# darwin-lora.net
KiCad netlist of a schematic drawn in EAGLE
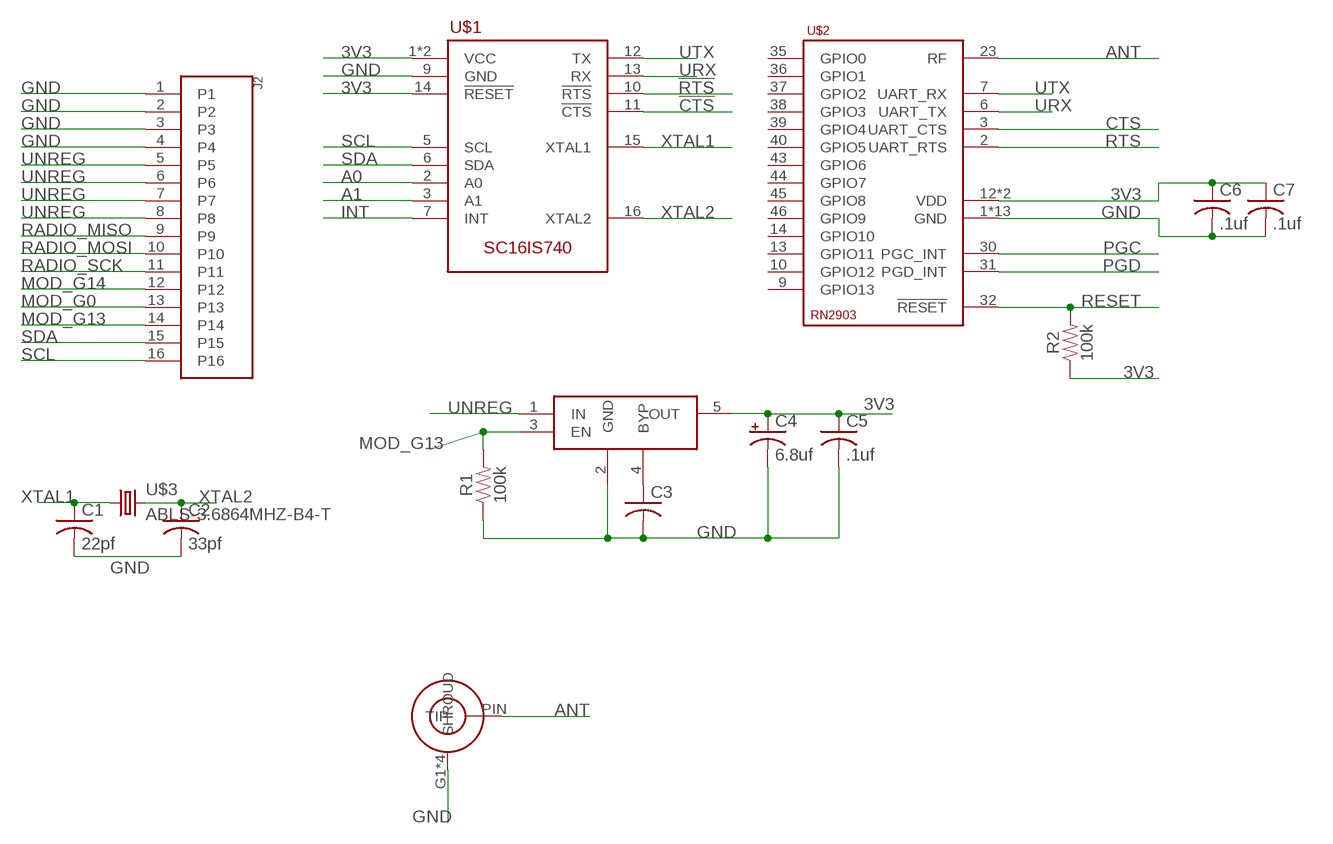
[diagram p0: schematic, sheet 1]

(export (version "E")
  (design (tool "Eeschema 10.0.6"))
  (components
    (comp (ref "C1")
      (value "22pf")
      (footprint "eagle-import:C0603K")
      (libsource (lib "eagle-import") (part "C-USC0603K"))
    )
    (comp (ref "C2")
      (value "33pf")
      (footprint "eagle-import:C0603K")
      (libsource (lib "eagle-import") (part "C-USC0603K"))
    )
    (comp (ref "C3")
      (value "C-USC0603K")
      (footprint "eagle-import:C0603K")
      (libsource (lib "eagle-import") (part "C-USC0603K"))
    )
    (comp (ref "C4")
      (value "6.8uf")
      (footprint "eagle-import:A_3216-18R")
      (libsource (lib "eagle-import") (part "CPOL-USA/3216-18R"))
    )
    (comp (ref "C5")
      (value ".1uf")
      (footprint "eagle-import:C0603K")
      (libsource (lib "eagle-import") (part "C-USC0603K"))
    )
    (comp (ref "C6")
      (value ".1uf")
      (footprint "eagle-import:C0603K")
      (libsource (lib "eagle-import") (part "C-USC0603K"))
    )
    (comp (ref "C7")
      (value ".1uf")
      (footprint "eagle-import:C0603K")
      (libsource (lib "eagle-import") (part "C-USC0603K"))
    )
    (comp (ref "J2")
      (value "505110-1692")
      (footprint "eagle-import:505110-1692")
      (libsource (lib "eagle-import") (part "505110-1692"))
    )
    (comp (ref "R1")
      (value "100k")
      (footprint "eagle-import:0603")
      (libsource (lib "eagle-import") (part "100KOHM-0603-1/10W-1%"))
    )
    (comp (ref "R2")
      (value "100k")
      (footprint "eagle-import:0603")
      (libsource (lib "eagle-import") (part "100KOHM-0603-1/10W-1%"))
    )
    (comp (ref "U$1")
      (value "SC16IS740")
      (footprint "eagle-import:SOP65P640X110-16")
      (libsource (lib "eagle-import") (part "SC16IS740"))
    )
    (comp (ref "U$2")
      (value "RN2903")
      (footprint "eagle-import:RN2903")
      (libsource (lib "eagle-import") (part "RN2903"))
    )
    (comp (ref "U$3")
      (value "ABLS-3.6864MHZ-B4-T")
      (footprint "eagle-import:ABLS")
      (libsource (lib "eagle-import") (part "ABLS-3.6864MHZ-B4-T"))
    )
    (comp (ref "U$4")
      (value "MIC5219-3.3YM5-TR")
      (footprint "eagle-import:SOT95P280X145-5")
      (libsource (lib "eagle-import") (part "MIC5219-3.3YM5-TR"))
    )
    (comp (ref "U$5")
      (value "5-1814832-1")
      (footprint "eagle-import:5-1814832-1")
      (libsource (lib "eagle-import") (part "5-1814832-1"))
    )
  )
  (nets
    (net (code "1") (name "/3V3") (class "Default")
      (node (ref "C4") (pin "+") (pinfunction "+_+") (pintype "passive"))
      (node (ref "C5") (pin "1") (pinfunction "1_1") (pintype "passive"))
      (node (ref "C6") (pin "1") (pinfunction "1_1") (pintype "passive"))
      (node (ref "C7") (pin "1") (pinfunction "1_1") (pintype "passive"))
      (node (ref "R2") (pin "1") (pinfunction "1_1") (pintype "passive"))
      (node (ref "U$1") (pin "1") (pinfunction "VCC_1") (pintype "bidirectional"))
      (node (ref "U$1") (pin "14") (pinfunction "~{RESET}_14") (pintype "bidirectional"))
      (node (ref "U$1") (pin "8") (pinfunction "VCC_8") (pintype "bidirectional"))
      (node (ref "U$2") (pin "12") (pinfunction "VDD_12") (pintype "bidirectional"))
      (node (ref "U$2") (pin "34") (pinfunction "VDD_34") (pintype "bidirectional"))
      (node (ref "U$4") (pin "5") (pinfunction "OUT_5") (pintype "bidirectional"))
    )
    (net (code "2") (name "/A0") (class "Default")
      (node (ref "U$1") (pin "2") (pinfunction "A0_2") (pintype "bidirectional"))
    )
    (net (code "3") (name "/A1") (class "Default")
      (node (ref "U$1") (pin "3") (pinfunction "A1_3") (pintype "bidirectional"))
    )
    (net (code "4") (name "/ANT") (class "Default")
      (node (ref "U$2") (pin "23") (pinfunction "RF_23") (pintype "bidirectional"))
      (node (ref "U$5") (pin "PIN") (pinfunction "TIP_PIN") (pintype "bidirectional"))
    )
    (net (code "5") (name "/CTS") (class "Default")
      (node (ref "U$2") (pin "3") (pinfunction "UART_CTS_3") (pintype "bidirectional"))
    )
    (net (code "6") (name "/GND") (class "Default")
      (node (ref "C1") (pin "2") (pinfunction "2_2") (pintype "passive"))
      (node (ref "C2") (pin "2") (pinfunction "2_2") (pintype "passive"))
      (node (ref "C3") (pin "2") (pinfunction "2_2") (pintype "passive"))
      (node (ref "C4") (pin "-") (pinfunction "-_-") (pintype "passive"))
      (node (ref "C5") (pin "2") (pinfunction "2_2") (pintype "passive"))
      (node (ref "C6") (pin "2") (pinfunction "2_2") (pintype "passive"))
      (node (ref "C7") (pin "2") (pinfunction "2_2") (pintype "passive"))
      (node (ref "J2") (pin "1") (pinfunction "P1_1") (pintype "bidirectional"))
      (node (ref "J2") (pin "2") (pinfunction "P2_2") (pintype "bidirectional"))
      (node (ref "J2") (pin "3") (pinfunction "P3_3") (pintype "bidirectional"))
      (node (ref "J2") (pin "4") (pinfunction "P4_4") (pintype "bidirectional"))
      (node (ref "R1") (pin "1") (pinfunction "1_1") (pintype "passive"))
      (node (ref "U$1") (pin "9") (pinfunction "GND_9") (pintype "bidirectional"))
      (node (ref "U$2") (pin "1") (pinfunction "GND_1") (pintype "bidirectional"))
      (node (ref "U$2") (pin "11") (pinfunction "GND_11") (pintype "bidirectional"))
      (node (ref "U$2") (pin "20") (pinfunction "GND_20") (pintype "bidirectional"))
      (node (ref "U$2") (pin "21") (pinfunction "GND_21") (pintype "bidirectional"))
      (node (ref "U$2") (pin "22") (pinfunction "GND_22") (pintype "bidirectional"))
      (node (ref "U$2") (pin "24") (pinfunction "GND_24") (pintype "bidirectional"))
      (node (ref "U$2") (pin "26") (pinfunction "GND_26") (pintype "bidirectional"))
      (node (ref "U$2") (pin "27") (pinfunction "GND_27") (pintype "bidirectional"))
      (node (ref "U$2") (pin "28") (pinfunction "GND_28") (pintype "bidirectional"))
      (node (ref "U$2") (pin "33") (pinfunction "GND_33") (pintype "bidirectional"))
      (node (ref "U$2") (pin "41") (pinfunction "GND_41") (pintype "bidirectional"))
      (node (ref "U$2") (pin "47") (pinfunction "GND_47") (pintype "bidirectional"))
      (node (ref "U$2") (pin "8") (pinfunction "GND_8") (pintype "bidirectional"))
      (node (ref "U$4") (pin "2") (pinfunction "GND_2") (pintype "bidirectional"))
      (node (ref "U$5") (pin "G1") (pinfunction "SHROUD_G1") (pintype "bidirectional"))
      (node (ref "U$5") (pin "G2") (pinfunction "SHROUD_G2") (pintype "bidirectional"))
      (node (ref "U$5") (pin "G3") (pinfunction "SHROUD_G3") (pintype "bidirectional"))
      (node (ref "U$5") (pin "G4") (pinfunction "SHROUD_G4") (pintype "bidirectional"))
    )
    (net (code "7") (name "/INT") (class "Default")
      (node (ref "U$1") (pin "7") (pinfunction "INT_7") (pintype "bidirectional"))
    )
    (net (code "8") (name "/MOD_G0") (class "Default")
      (node (ref "J2") (pin "13") (pinfunction "P13_13") (pintype "bidirectional"))
    )
    (net (code "9") (name "/MOD_G13") (class "Default")
      (node (ref "J2") (pin "14") (pinfunction "P14_14") (pintype "bidirectional"))
      (node (ref "R1") (pin "2") (pinfunction "2_2") (pintype "passive"))
      (node (ref "U$4") (pin "3") (pinfunction "EN_3") (pintype "bidirectional"))
    )
    (net (code "10") (name "/MOD_G14") (class "Default")
      (node (ref "J2") (pin "12") (pinfunction "P12_12") (pintype "bidirectional"))
    )
    (net (code "11") (name "/PGC") (class "Default")
      (node (ref "U$2") (pin "30") (pinfunction "PGC_INT_30") (pintype "bidirectional"))
    )
    (net (code "12") (name "/PGD") (class "Default")
      (node (ref "U$2") (pin "31") (pinfunction "PGD_INT_31") (pintype "bidirectional"))
    )
    (net (code "13") (name "/RADIO_MISO") (class "Default")
      (node (ref "J2") (pin "9") (pinfunction "P9_9") (pintype "bidirectional"))
    )
    (net (code "14") (name "/RADIO_MOSI") (class "Default")
      (node (ref "J2") (pin "10") (pinfunction "P10_10") (pintype "bidirectional"))
    )
    (net (code "15") (name "/RADIO_SCK") (class "Default")
      (node (ref "J2") (pin "11") (pinfunction "P11_11") (pintype "bidirectional"))
    )
    (net (code "16") (name "/RESET") (class "Default")
      (node (ref "R2") (pin "2") (pinfunction "2_2") (pintype "passive"))
      (node (ref "U$2") (pin "32") (pinfunction "~{RESET}_32") (pintype "bidirectional"))
    )
    (net (code "17") (name "/RTS") (class "Default")
      (node (ref "U$2") (pin "2") (pinfunction "UART_RTS_2") (pintype "bidirectional"))
    )
    (net (code "18") (name "/SCL") (class "Default")
      (node (ref "J2") (pin "16") (pinfunction "P16_16") (pintype "bidirectional"))
      (node (ref "U$1") (pin "5") (pinfunction "SCL_5") (pintype "bidirectional"))
    )
    (net (code "19") (name "/SDA") (class "Default")
      (node (ref "J2") (pin "15") (pinfunction "P15_15") (pintype "bidirectional"))
      (node (ref "U$1") (pin "6") (pinfunction "SDA_6") (pintype "bidirectional"))
    )
    (net (code "20") (name "/UNREG") (class "Default")
      (node (ref "J2") (pin "5") (pinfunction "P5_5") (pintype "bidirectional"))
      (node (ref "J2") (pin "6") (pinfunction "P6_6") (pintype "bidirectional"))
      (node (ref "J2") (pin "7") (pinfunction "P7_7") (pintype "bidirectional"))
      (node (ref "J2") (pin "8") (pinfunction "P8_8") (pintype "bidirectional"))
      (node (ref "U$4") (pin "1") (pinfunction "IN_1") (pintype "bidirectional"))
    )
    (net (code "21") (name "/URX") (class "Default")
      (node (ref "U$1") (pin "13") (pinfunction "RX_13") (pintype "bidirectional"))
      (node (ref "U$2") (pin "6") (pinfunction "UART_TX_6") (pintype "bidirectional"))
    )
    (net (code "22") (name "/UTX") (class "Default")
      (node (ref "U$1") (pin "12") (pinfunction "TX_12") (pintype "bidirectional"))
      (node (ref "U$2") (pin "7") (pinfunction "UART_RX_7") (pintype "bidirectional"))
    )
    (net (code "23") (name "/XTAL1") (class "Default")
      (node (ref "C1") (pin "1") (pinfunction "1_1") (pintype "passive"))
      (node (ref "U$1") (pin "15") (pinfunction "XTAL1_15") (pintype "bidirectional"))
      (node (ref "U$3") (pin "P$1") (pinfunction "1_P$1") (pintype "passive"))
    )
    (net (code "24") (name "/XTAL2") (class "Default")
      (node (ref "C2") (pin "1") (pinfunction "1_1") (pintype "passive"))
      (node (ref "U$1") (pin "16") (pinfunction "XTAL2_16") (pintype "bidirectional"))
      (node (ref "U$3") (pin "P$2") (pinfunction "2_P$2") (pintype "passive"))
    )
    (net (code "25") (name "/~{CTS}") (class "Default")
      (node (ref "U$1") (pin "11") (pinfunction "~{CTS}_11") (pintype "bidirectional"))
    )
    (net (code "26") (name "/~{RTS}") (class "Default")
      (node (ref "U$1") (pin "10") (pinfunction "~{RTS}_10") (pintype "bidirectional"))
    )
    (net (code "27") (name "Net-(U$4-BYP)") (class "Default")
      (node (ref "C3") (pin "1") (pinfunction "1_1") (pintype "passive"))
      (node (ref "U$4") (pin "4") (pinfunction "BYP_4") (pintype "bidirectional"))
    )
    (net (code "28") (name "unconnected-(U$2-GPIO0-Pad35)") (class "Default")
      (node (ref "U$2") (pin "35") (pinfunction "GPIO0_35") (pintype "bidirectional"))
    )
    (net (code "29") (name "unconnected-(U$2-GPIO1-Pad36)") (class "Default")
      (node (ref "U$2") (pin "36") (pinfunction "GPIO1_36") (pintype "bidirectional"))
    )
    (net (code "30") (name "unconnected-(U$2-GPIO2-Pad37)") (class "Default")
      (node (ref "U$2") (pin "37") (pinfunction "GPIO2_37") (pintype "bidirectional"))
    )
    (net (code "31") (name "unconnected-(U$2-GPIO3-Pad38)") (class "Default")
      (node (ref "U$2") (pin "38") (pinfunction "GPIO3_38") (pintype "bidirectional"))
    )
    (net (code "32") (name "unconnected-(U$2-GPIO4-Pad39)") (class "Default")
      (node (ref "U$2") (pin "39") (pinfunction "GPIO4_39") (pintype "bidirectional"))
    )
    (net (code "33") (name "unconnected-(U$2-GPIO5-Pad40)") (class "Default")
      (node (ref "U$2") (pin "40") (pinfunction "GPIO5_40") (pintype "bidirectional"))
    )
    (net (code "34") (name "unconnected-(U$2-GPIO6-Pad43)") (class "Default")
      (node (ref "U$2") (pin "43") (pinfunction "GPIO6_43") (pintype "bidirectional"))
    )
    (net (code "35") (name "unconnected-(U$2-GPIO7-Pad44)") (class "Default")
      (node (ref "U$2") (pin "44") (pinfunction "GPIO7_44") (pintype "bidirectional"))
    )
    (net (code "36") (name "unconnected-(U$2-GPIO8-Pad45)") (class "Default")
      (node (ref "U$2") (pin "45") (pinfunction "GPIO8_45") (pintype "bidirectional"))
    )
    (net (code "37") (name "unconnected-(U$2-GPIO9-Pad46)") (class "Default")
      (node (ref "U$2") (pin "46") (pinfunction "GPIO9_46") (pintype "bidirectional"))
    )
    (net (code "38") (name "unconnected-(U$2-GPIO10-Pad14)") (class "Default")
      (node (ref "U$2") (pin "14") (pinfunction "GPIO10_14") (pintype "bidirectional"))
    )
    (net (code "39") (name "unconnected-(U$2-GPIO11-Pad13)") (class "Default")
      (node (ref "U$2") (pin "13") (pinfunction "GPIO11_13") (pintype "bidirectional"))
    )
    (net (code "40") (name "unconnected-(U$2-GPIO12-Pad10)") (class "Default")
      (node (ref "U$2") (pin "10") (pinfunction "GPIO12_10") (pintype "bidirectional"))
    )
    (net (code "41") (name "unconnected-(U$2-GPIO13-Pad9)") (class "Default")
      (node (ref "U$2") (pin "9") (pinfunction "GPIO13_9") (pintype "bidirectional"))
    )
  )
)
